# bbb_cape.net
KiCad netlist of a schematic drawn in EAGLE
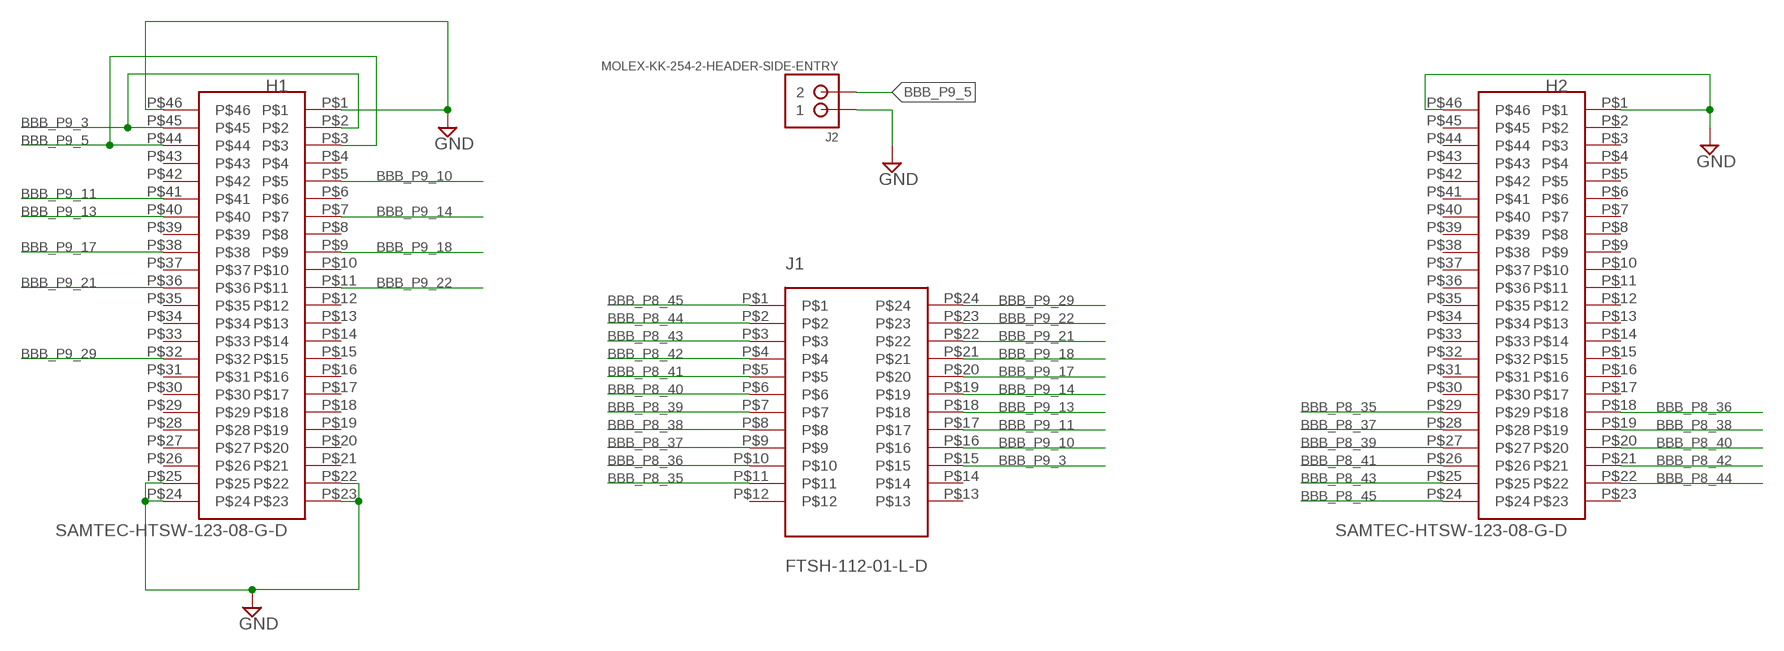
[diagram p0: schematic, sheet 1]

(export (version "E")
  (design (tool "Eeschema 10.0.6"))
  (components
    (comp (ref "H1")
      (value "SAMTEC-HTSW-123-08-G-D")
      (footprint "eagle-import:HEADER-2X23-0.1-INCH")
      (libsource (lib "eagle-import") (part "HEADER-2X23"))
    )
    (comp (ref "H2")
      (value "SAMTEC-HTSW-123-08-G-D")
      (footprint "eagle-import:HEADER-2X23-0.1-INCH")
      (libsource (lib "eagle-import") (part "HEADER-2X23"))
    )
    (comp (ref "J1")
      (value "FTSH-112-01-L-D")
      (footprint "eagle-import:FTSH-112-01-L-D")
      (libsource (lib "eagle-import") (part "FTSH-112-CONNSTRAIGHT"))
    )
    (comp (ref "J2")
      (value "MOLEX-KK-254-2-HEADER-SIDE-ENTRY")
      (footprint "eagle-import:MOLEX-KK-254-2-HEADER-SIDE-ENTRY")
      (libsource (lib "eagle-import") (part "MOLEX-KK-254-2-HEADER-SIDE-ENTRY"))
    )
  )
  (nets
    (net (code "1") (name "/BBB_P8_35") (class "Default")
      (node (ref "H2") (pin "P$29") (pinfunction "P$29_P$29") (pintype "bidirectional"))
      (node (ref "J1") (pin "P$11") (pinfunction "P$11_P$11") (pintype "bidirectional"))
    )
    (net (code "2") (name "/BBB_P8_36") (class "Default")
      (node (ref "H2") (pin "P$18") (pinfunction "P$18_P$18") (pintype "bidirectional"))
      (node (ref "J1") (pin "P$10") (pinfunction "P$10_P$10") (pintype "bidirectional"))
    )
    (net (code "3") (name "/BBB_P8_37") (class "Default")
      (node (ref "H2") (pin "P$28") (pinfunction "P$28_P$28") (pintype "bidirectional"))
      (node (ref "J1") (pin "P$9") (pinfunction "P$9_P$9") (pintype "bidirectional"))
    )
    (net (code "4") (name "/BBB_P8_38") (class "Default")
      (node (ref "H2") (pin "P$19") (pinfunction "P$19_P$19") (pintype "bidirectional"))
      (node (ref "J1") (pin "P$8") (pinfunction "P$8_P$8") (pintype "bidirectional"))
    )
    (net (code "5") (name "/BBB_P8_39") (class "Default")
      (node (ref "H2") (pin "P$27") (pinfunction "P$27_P$27") (pintype "bidirectional"))
      (node (ref "J1") (pin "P$7") (pinfunction "P$7_P$7") (pintype "bidirectional"))
    )
    (net (code "6") (name "/BBB_P8_40") (class "Default")
      (node (ref "H2") (pin "P$20") (pinfunction "P$20_P$20") (pintype "bidirectional"))
      (node (ref "J1") (pin "P$6") (pinfunction "P$6_P$6") (pintype "bidirectional"))
    )
    (net (code "7") (name "/BBB_P8_41") (class "Default")
      (node (ref "H2") (pin "P$26") (pinfunction "P$26_P$26") (pintype "bidirectional"))
      (node (ref "J1") (pin "P$5") (pinfunction "P$5_P$5") (pintype "bidirectional"))
    )
    (net (code "8") (name "/BBB_P8_42") (class "Default")
      (node (ref "H2") (pin "P$21") (pinfunction "P$21_P$21") (pintype "bidirectional"))
      (node (ref "J1") (pin "P$4") (pinfunction "P$4_P$4") (pintype "bidirectional"))
    )
    (net (code "9") (name "/BBB_P8_43") (class "Default")
      (node (ref "H2") (pin "P$25") (pinfunction "P$25_P$25") (pintype "bidirectional"))
      (node (ref "J1") (pin "P$3") (pinfunction "P$3_P$3") (pintype "bidirectional"))
    )
    (net (code "10") (name "/BBB_P8_44") (class "Default")
      (node (ref "H2") (pin "P$22") (pinfunction "P$22_P$22") (pintype "bidirectional"))
      (node (ref "J1") (pin "P$2") (pinfunction "P$2_P$2") (pintype "bidirectional"))
    )
    (net (code "11") (name "/BBB_P8_45") (class "Default")
      (node (ref "H2") (pin "P$24") (pinfunction "P$24_P$24") (pintype "bidirectional"))
      (node (ref "J1") (pin "P$1") (pinfunction "P$1_P$1") (pintype "bidirectional"))
    )
    (net (code "12") (name "/BBB_P9_3") (class "Default")
      (node (ref "H1") (pin "P$2") (pinfunction "P$2_P$2") (pintype "bidirectional"))
      (node (ref "H1") (pin "P$45") (pinfunction "P$45_P$45") (pintype "bidirectional"))
      (node (ref "J1") (pin "P$15") (pinfunction "P$15_P$15") (pintype "bidirectional"))
    )
    (net (code "13") (name "/BBB_P9_10") (class "Default")
      (node (ref "H1") (pin "P$5") (pinfunction "P$5_P$5") (pintype "bidirectional"))
      (node (ref "J1") (pin "P$16") (pinfunction "P$16_P$16") (pintype "bidirectional"))
    )
    (net (code "14") (name "/BBB_P9_11") (class "Default")
      (node (ref "H1") (pin "P$41") (pinfunction "P$41_P$41") (pintype "bidirectional"))
      (node (ref "J1") (pin "P$17") (pinfunction "P$17_P$17") (pintype "bidirectional"))
    )
    (net (code "15") (name "/BBB_P9_13") (class "Default")
      (node (ref "H1") (pin "P$40") (pinfunction "P$40_P$40") (pintype "bidirectional"))
      (node (ref "J1") (pin "P$18") (pinfunction "P$18_P$18") (pintype "bidirectional"))
    )
    (net (code "16") (name "/BBB_P9_14") (class "Default")
      (node (ref "H1") (pin "P$7") (pinfunction "P$7_P$7") (pintype "bidirectional"))
      (node (ref "J1") (pin "P$19") (pinfunction "P$19_P$19") (pintype "bidirectional"))
    )
    (net (code "17") (name "/BBB_P9_17") (class "Default")
      (node (ref "H1") (pin "P$38") (pinfunction "P$38_P$38") (pintype "bidirectional"))
      (node (ref "J1") (pin "P$20") (pinfunction "P$20_P$20") (pintype "bidirectional"))
    )
    (net (code "18") (name "/BBB_P9_18") (class "Default")
      (node (ref "H1") (pin "P$9") (pinfunction "P$9_P$9") (pintype "bidirectional"))
      (node (ref "J1") (pin "P$21") (pinfunction "P$21_P$21") (pintype "bidirectional"))
    )
    (net (code "19") (name "/BBB_P9_21") (class "Default")
      (node (ref "H1") (pin "P$36") (pinfunction "P$36_P$36") (pintype "bidirectional"))
      (node (ref "J1") (pin "P$22") (pinfunction "P$22_P$22") (pintype "bidirectional"))
    )
    (net (code "20") (name "/BBB_P9_22") (class "Default")
      (node (ref "H1") (pin "P$11") (pinfunction "P$11_P$11") (pintype "bidirectional"))
      (node (ref "J1") (pin "P$23") (pinfunction "P$23_P$23") (pintype "bidirectional"))
    )
    (net (code "21") (name "/BBB_P9_29") (class "Default")
      (node (ref "H1") (pin "P$32") (pinfunction "P$32_P$32") (pintype "bidirectional"))
      (node (ref "J1") (pin "P$24") (pinfunction "P$24_P$24") (pintype "bidirectional"))
    )
    (net (code "22") (name "BBB_P9_5") (class "Default")
      (node (ref "H1") (pin "P$3") (pinfunction "P$3_P$3") (pintype "bidirectional"))
      (node (ref "H1") (pin "P$44") (pinfunction "P$44_P$44") (pintype "bidirectional"))
      (node (ref "J2") (pin "P$2") (pinfunction "2_P$2") (pintype "bidirectional"))
    )
    (net (code "23") (name "GND") (class "Default")
      (node (ref "H1") (pin "P$1") (pinfunction "P$1_P$1") (pintype "bidirectional"))
      (node (ref "H1") (pin "P$22") (pinfunction "P$22_P$22") (pintype "bidirectional"))
      (node (ref "H1") (pin "P$23") (pinfunction "P$23_P$23") (pintype "bidirectional"))
      (node (ref "H1") (pin "P$24") (pinfunction "P$24_P$24") (pintype "bidirectional"))
      (node (ref "H1") (pin "P$25") (pinfunction "P$25_P$25") (pintype "bidirectional"))
      (node (ref "H1") (pin "P$46") (pinfunction "P$46_P$46") (pintype "bidirectional"))
      (node (ref "H2") (pin "P$1") (pinfunction "P$1_P$1") (pintype "bidirectional"))
      (node (ref "H2") (pin "P$46") (pinfunction "P$46_P$46") (pintype "bidirectional"))
      (node (ref "J2") (pin "P$1") (pinfunction "1_P$1") (pintype "bidirectional"))
    )
    (net (code "24") (name "unconnected-(H1-PadP$4)") (class "Default")
      (node (ref "H1") (pin "P$4") (pinfunction "P$4_P$4") (pintype "bidirectional"))
    )
    (net (code "25") (name "unconnected-(H1-PadP$6)") (class "Default")
      (node (ref "H1") (pin "P$6") (pinfunction "P$6_P$6") (pintype "bidirectional"))
    )
    (net (code "26") (name "unconnected-(H1-PadP$8)") (class "Default")
      (node (ref "H1") (pin "P$8") (pinfunction "P$8_P$8") (pintype "bidirectional"))
    )
    (net (code "27") (name "unconnected-(H1-PadP$10)") (class "Default")
      (node (ref "H1") (pin "P$10") (pinfunction "P$10_P$10") (pintype "bidirectional"))
    )
    (net (code "28") (name "unconnected-(H1-PadP$12)") (class "Default")
      (node (ref "H1") (pin "P$12") (pinfunction "P$12_P$12") (pintype "bidirectional"))
    )
    (net (code "29") (name "unconnected-(H1-PadP$13)") (class "Default")
      (node (ref "H1") (pin "P$13") (pinfunction "P$13_P$13") (pintype "bidirectional"))
    )
    (net (code "30") (name "unconnected-(H1-PadP$14)") (class "Default")
      (node (ref "H1") (pin "P$14") (pinfunction "P$14_P$14") (pintype "bidirectional"))
    )
    (net (code "31") (name "unconnected-(H1-PadP$15)") (class "Default")
      (node (ref "H1") (pin "P$15") (pinfunction "P$15_P$15") (pintype "bidirectional"))
    )
    (net (code "32") (name "unconnected-(H1-PadP$16)") (class "Default")
      (node (ref "H1") (pin "P$16") (pinfunction "P$16_P$16") (pintype "bidirectional"))
    )
    (net (code "33") (name "unconnected-(H1-PadP$17)") (class "Default")
      (node (ref "H1") (pin "P$17") (pinfunction "P$17_P$17") (pintype "bidirectional"))
    )
    (net (code "34") (name "unconnected-(H1-PadP$18)") (class "Default")
      (node (ref "H1") (pin "P$18") (pinfunction "P$18_P$18") (pintype "bidirectional"))
    )
    (net (code "35") (name "unconnected-(H1-PadP$19)") (class "Default")
      (node (ref "H1") (pin "P$19") (pinfunction "P$19_P$19") (pintype "bidirectional"))
    )
    (net (code "36") (name "unconnected-(H1-PadP$20)") (class "Default")
      (node (ref "H1") (pin "P$20") (pinfunction "P$20_P$20") (pintype "bidirectional"))
    )
    (net (code "37") (name "unconnected-(H1-PadP$21)") (class "Default")
      (node (ref "H1") (pin "P$21") (pinfunction "P$21_P$21") (pintype "bidirectional"))
    )
    (net (code "38") (name "unconnected-(H1-PadP$26)") (class "Default")
      (node (ref "H1") (pin "P$26") (pinfunction "P$26_P$26") (pintype "bidirectional"))
    )
    (net (code "39") (name "unconnected-(H1-PadP$27)") (class "Default")
      (node (ref "H1") (pin "P$27") (pinfunction "P$27_P$27") (pintype "bidirectional"))
    )
    (net (code "40") (name "unconnected-(H1-PadP$28)") (class "Default")
      (node (ref "H1") (pin "P$28") (pinfunction "P$28_P$28") (pintype "bidirectional"))
    )
    (net (code "41") (name "unconnected-(H1-PadP$29)") (class "Default")
      (node (ref "H1") (pin "P$29") (pinfunction "P$29_P$29") (pintype "bidirectional"))
    )
    (net (code "42") (name "unconnected-(H1-PadP$30)") (class "Default")
      (node (ref "H1") (pin "P$30") (pinfunction "P$30_P$30") (pintype "bidirectional"))
    )
    (net (code "43") (name "unconnected-(H1-PadP$31)") (class "Default")
      (node (ref "H1") (pin "P$31") (pinfunction "P$31_P$31") (pintype "bidirectional"))
    )
    (net (code "44") (name "unconnected-(H1-PadP$33)") (class "Default")
      (node (ref "H1") (pin "P$33") (pinfunction "P$33_P$33") (pintype "bidirectional"))
    )
    (net (code "45") (name "unconnected-(H1-PadP$34)") (class "Default")
      (node (ref "H1") (pin "P$34") (pinfunction "P$34_P$34") (pintype "bidirectional"))
    )
    (net (code "46") (name "unconnected-(H1-PadP$35)") (class "Default")
      (node (ref "H1") (pin "P$35") (pinfunction "P$35_P$35") (pintype "bidirectional"))
    )
    (net (code "47") (name "unconnected-(H1-PadP$37)") (class "Default")
      (node (ref "H1") (pin "P$37") (pinfunction "P$37_P$37") (pintype "bidirectional"))
    )
    (net (code "48") (name "unconnected-(H1-PadP$39)") (class "Default")
      (node (ref "H1") (pin "P$39") (pinfunction "P$39_P$39") (pintype "bidirectional"))
    )
    (net (code "49") (name "unconnected-(H1-PadP$42)") (class "Default")
      (node (ref "H1") (pin "P$42") (pinfunction "P$42_P$42") (pintype "bidirectional"))
    )
    (net (code "50") (name "unconnected-(H1-PadP$43)") (class "Default")
      (node (ref "H1") (pin "P$43") (pinfunction "P$43_P$43") (pintype "bidirectional"))
    )
    (net (code "51") (name "unconnected-(H2-PadP$2)") (class "Default")
      (node (ref "H2") (pin "P$2") (pinfunction "P$2_P$2") (pintype "bidirectional"))
    )
    (net (code "52") (name "unconnected-(H2-PadP$3)") (class "Default")
      (node (ref "H2") (pin "P$3") (pinfunction "P$3_P$3") (pintype "bidirectional"))
    )
    (net (code "53") (name "unconnected-(H2-PadP$4)") (class "Default")
      (node (ref "H2") (pin "P$4") (pinfunction "P$4_P$4") (pintype "bidirectional"))
    )
    (net (code "54") (name "unconnected-(H2-PadP$5)") (class "Default")
      (node (ref "H2") (pin "P$5") (pinfunction "P$5_P$5") (pintype "bidirectional"))
    )
    (net (code "55") (name "unconnected-(H2-PadP$6)") (class "Default")
      (node (ref "H2") (pin "P$6") (pinfunction "P$6_P$6") (pintype "bidirectional"))
    )
    (net (code "56") (name "unconnected-(H2-PadP$7)") (class "Default")
      (node (ref "H2") (pin "P$7") (pinfunction "P$7_P$7") (pintype "bidirectional"))
    )
    (net (code "57") (name "unconnected-(H2-PadP$8)") (class "Default")
      (node (ref "H2") (pin "P$8") (pinfunction "P$8_P$8") (pintype "bidirectional"))
    )
    (net (code "58") (name "unconnected-(H2-PadP$9)") (class "Default")
      (node (ref "H2") (pin "P$9") (pinfunction "P$9_P$9") (pintype "bidirectional"))
    )
    (net (code "59") (name "unconnected-(H2-PadP$10)") (class "Default")
      (node (ref "H2") (pin "P$10") (pinfunction "P$10_P$10") (pintype "bidirectional"))
    )
    (net (code "60") (name "unconnected-(H2-PadP$11)") (class "Default")
      (node (ref "H2") (pin "P$11") (pinfunction "P$11_P$11") (pintype "bidirectional"))
    )
    (net (code "61") (name "unconnected-(H2-PadP$12)") (class "Default")
      (node (ref "H2") (pin "P$12") (pinfunction "P$12_P$12") (pintype "bidirectional"))
    )
    (net (code "62") (name "unconnected-(H2-PadP$13)") (class "Default")
      (node (ref "H2") (pin "P$13") (pinfunction "P$13_P$13") (pintype "bidirectional"))
    )
    (net (code "63") (name "unconnected-(H2-PadP$14)") (class "Default")
      (node (ref "H2") (pin "P$14") (pinfunction "P$14_P$14") (pintype "bidirectional"))
    )
    (net (code "64") (name "unconnected-(H2-PadP$15)") (class "Default")
      (node (ref "H2") (pin "P$15") (pinfunction "P$15_P$15") (pintype "bidirectional"))
    )
    (net (code "65") (name "unconnected-(H2-PadP$16)") (class "Default")
      (node (ref "H2") (pin "P$16") (pinfunction "P$16_P$16") (pintype "bidirectional"))
    )
    (net (code "66") (name "unconnected-(H2-PadP$17)") (class "Default")
      (node (ref "H2") (pin "P$17") (pinfunction "P$17_P$17") (pintype "bidirectional"))
    )
    (net (code "67") (name "unconnected-(H2-PadP$23)") (class "Default")
      (node (ref "H2") (pin "P$23") (pinfunction "P$23_P$23") (pintype "bidirectional"))
    )
    (net (code "68") (name "unconnected-(H2-PadP$30)") (class "Default")
      (node (ref "H2") (pin "P$30") (pinfunction "P$30_P$30") (pintype "bidirectional"))
    )
    (net (code "69") (name "unconnected-(H2-PadP$31)") (class "Default")
      (node (ref "H2") (pin "P$31") (pinfunction "P$31_P$31") (pintype "bidirectional"))
    )
    (net (code "70") (name "unconnected-(H2-PadP$32)") (class "Default")
      (node (ref "H2") (pin "P$32") (pinfunction "P$32_P$32") (pintype "bidirectional"))
    )
    (net (code "71") (name "unconnected-(H2-PadP$33)") (class "Default")
      (node (ref "H2") (pin "P$33") (pinfunction "P$33_P$33") (pintype "bidirectional"))
    )
    (net (code "72") (name "unconnected-(H2-PadP$34)") (class "Default")
      (node (ref "H2") (pin "P$34") (pinfunction "P$34_P$34") (pintype "bidirectional"))
    )
    (net (code "73") (name "unconnected-(H2-PadP$35)") (class "Default")
      (node (ref "H2") (pin "P$35") (pinfunction "P$35_P$35") (pintype "bidirectional"))
    )
    (net (code "74") (name "unconnected-(H2-PadP$36)") (class "Default")
      (node (ref "H2") (pin "P$36") (pinfunction "P$36_P$36") (pintype "bidirectional"))
    )
    (net (code "75") (name "unconnected-(H2-PadP$37)") (class "Default")
      (node (ref "H2") (pin "P$37") (pinfunction "P$37_P$37") (pintype "bidirectional"))
    )
    (net (code "76") (name "unconnected-(H2-PadP$38)") (class "Default")
      (node (ref "H2") (pin "P$38") (pinfunction "P$38_P$38") (pintype "bidirectional"))
    )
    (net (code "77") (name "unconnected-(H2-PadP$39)") (class "Default")
      (node (ref "H2") (pin "P$39") (pinfunction "P$39_P$39") (pintype "bidirectional"))
    )
    (net (code "78") (name "unconnected-(H2-PadP$40)") (class "Default")
      (node (ref "H2") (pin "P$40") (pinfunction "P$40_P$40") (pintype "bidirectional"))
    )
    (net (code "79") (name "unconnected-(H2-PadP$41)") (class "Default")
      (node (ref "H2") (pin "P$41") (pinfunction "P$41_P$41") (pintype "bidirectional"))
    )
    (net (code "80") (name "unconnected-(H2-PadP$42)") (class "Default")
      (node (ref "H2") (pin "P$42") (pinfunction "P$42_P$42") (pintype "bidirectional"))
    )
    (net (code "81") (name "unconnected-(H2-PadP$43)") (class "Default")
      (node (ref "H2") (pin "P$43") (pinfunction "P$43_P$43") (pintype "bidirectional"))
    )
    (net (code "82") (name "unconnected-(H2-PadP$44)") (class "Default")
      (node (ref "H2") (pin "P$44") (pinfunction "P$44_P$44") (pintype "bidirectional"))
    )
    (net (code "83") (name "unconnected-(H2-PadP$45)") (class "Default")
      (node (ref "H2") (pin "P$45") (pinfunction "P$45_P$45") (pintype "bidirectional"))
    )
    (net (code "84") (name "unconnected-(J1-PadP$12)") (class "Default")
      (node (ref "J1") (pin "P$12") (pinfunction "P$12_P$12") (pintype "bidirectional"))
    )
    (net (code "85") (name "unconnected-(J1-PadP$13)") (class "Default")
      (node (ref "J1") (pin "P$13") (pinfunction "P$13_P$13") (pintype "bidirectional"))
    )
    (net (code "86") (name "unconnected-(J1-PadP$14)") (class "Default")
      (node (ref "J1") (pin "P$14") (pinfunction "P$14_P$14") (pintype "bidirectional"))
    )
  )
)
